# feeder_container_side.net
KiCad netlist of a schematic drawn in EAGLE
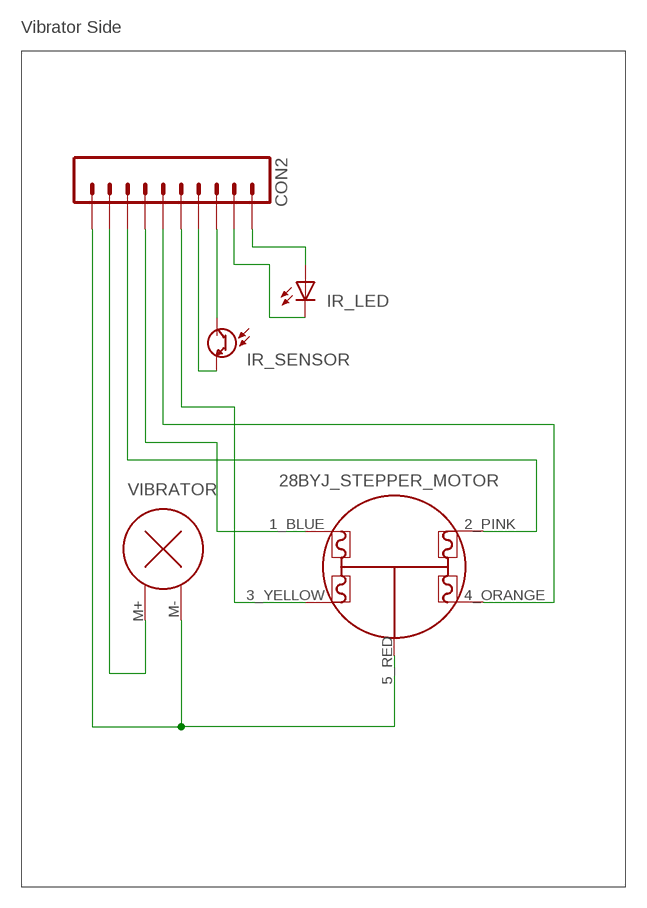
[diagram p0: schematic, sheet 1]

(export (version "E")
  (design (tool "Eeschema 10.0.6"))
  (components
    (comp (ref "28BYJ_STEPPER_MOTOR")
      (value "28BYJ")
      (footprint "eagle-import:28BYJ")
      (libsource (lib "eagle-import") (part "28BYJ"))
    )
    (comp (ref "CON2")
      (value "CON_10")
      (footprint "eagle-import:CON_10P_1.25_ALIEXPRESS")
      (libsource (lib "eagle-import") (part "CON_10"))
    )
    (comp (ref "IR_LED")
      (value "TCR5000_EMITTER")
      (footprint "eagle-import:TCR5000_IR_EMITTER")
      (libsource (lib "eagle-import") (part "TCR5000_EMITTER"))
    )
    (comp (ref "IR_SENSOR")
      (value "TCR5000_SENSOR")
      (footprint "eagle-import:TCR5000_IR_SENSOR")
      (libsource (lib "eagle-import") (part "TCR5000_SENSOR"))
    )
    (comp (ref "VIBRATOR")
      (value "VIBRATION_MOTORVIBRATION_MOTOR_LARGE")
      (footprint "eagle-import:VIBRATION_MOTOR_LARGE")
      (libsource (lib "eagle-import") (part "VIBRATION_MOTORVIBRATION_MOTOR_LARGE"))
    )
  )
  (nets
    (net (code "1") (name "Net-(28BYJ_STEPPER_MOTOR-1)") (class "Default")
      (node (ref "28BYJ_STEPPER_MOTOR") (pin "1_BLUE") (pinfunction "1_1_BLUE") (pintype "input"))
      (node (ref "CON2") (pin "7") (pinfunction "7_7") (pintype "passive"))
    )
    (net (code "2") (name "Net-(28BYJ_STEPPER_MOTOR-2)") (class "Default")
      (node (ref "28BYJ_STEPPER_MOTOR") (pin "2_PINK") (pinfunction "2_2_PINK") (pintype "input"))
      (node (ref "CON2") (pin "8") (pinfunction "8_8") (pintype "passive"))
    )
    (net (code "3") (name "Net-(28BYJ_STEPPER_MOTOR-3)") (class "Default")
      (node (ref "28BYJ_STEPPER_MOTOR") (pin "3_YELLOW") (pinfunction "3_3_YELLOW") (pintype "input"))
      (node (ref "CON2") (pin "5") (pinfunction "5_5") (pintype "passive"))
    )
    (net (code "4") (name "Net-(28BYJ_STEPPER_MOTOR-4)") (class "Default")
      (node (ref "28BYJ_STEPPER_MOTOR") (pin "4_ORANGE") (pinfunction "4_4_ORANGE") (pintype "input"))
      (node (ref "CON2") (pin "6") (pinfunction "6_6") (pintype "passive"))
    )
    (net (code "5") (name "Net-(28BYJ_STEPPER_MOTOR-5_COM)") (class "Default")
      (node (ref "28BYJ_STEPPER_MOTOR") (pin "5_RED") (pinfunction "5_COM_5_RED") (pintype "bidirectional"))
      (node (ref "CON2") (pin "10") (pinfunction "10_10") (pintype "passive"))
      (node (ref "VIBRATOR") (pin "M-") (pinfunction "-_M-") (pintype "bidirectional"))
    )
    (net (code "6") (name "Net-(CON2-Pad1)") (class "Default")
      (node (ref "CON2") (pin "1") (pinfunction "1_1") (pintype "passive"))
      (node (ref "IR_LED") (pin "A") (pinfunction "A_A") (pintype "passive"))
    )
    (net (code "7") (name "Net-(CON2-Pad2)") (class "Default")
      (node (ref "CON2") (pin "2") (pinfunction "2_2") (pintype "passive"))
      (node (ref "IR_LED") (pin "C") (pinfunction "C_C") (pintype "passive"))
    )
    (net (code "8") (name "Net-(CON2-Pad3)") (class "Default")
      (node (ref "CON2") (pin "3") (pinfunction "3_3") (pintype "passive"))
      (node (ref "IR_SENSOR") (pin "C") (pinfunction "C_C") (pintype "passive"))
    )
    (net (code "9") (name "Net-(CON2-Pad4)") (class "Default")
      (node (ref "CON2") (pin "4") (pinfunction "4_4") (pintype "passive"))
      (node (ref "IR_SENSOR") (pin "E") (pinfunction "E_E") (pintype "passive"))
    )
    (net (code "10") (name "Net-(VIBRATOR-+)") (class "Default")
      (node (ref "CON2") (pin "9") (pinfunction "9_9") (pintype "passive"))
      (node (ref "VIBRATOR") (pin "M+") (pinfunction "+_M+") (pintype "bidirectional"))
    )
  )
)
